# FULL_CB_Servo_REV_C.net
KiCad netlist of a schematic drawn in Altium Designer
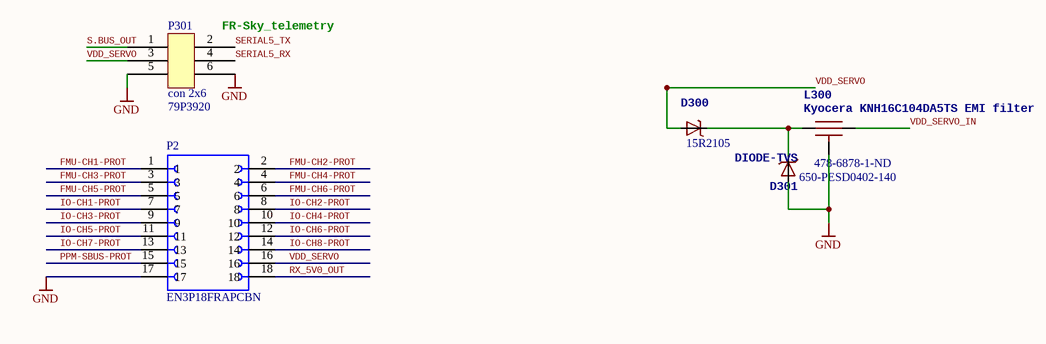
[diagram p0: FULL_CB_Servo_REV_C.SchDoc]

(export (version "E")
  (design (tool "Eeschema 10.0.6"))
  (components
    (comp (ref "D300")
      (value "MSS1P4-M3")
      (footprint "MICROSMP")
      (description "Diode, Schottky, 40V, 1A, MicroSMP, SMD")
      (fields (field (name "SUPPLIER PART NUMBER 1") "15R2105"))
      (libsource (lib "CB_REV_C") (part "DIODE-SCHOTTKY_MSMP"))
    )
    (comp (ref "D301")
      (value "DIODE-TVS")
      (footprint "0402-TVS")
      (description "Diode, TVS, 14VWM, 40VC, 0402, SMD")
      (fields (field (name "SUPPLIER PART NUMBER 1") "650-PESD0402-140"))
      (libsource (lib "CB_REV_C") (part "DIODE-TVS"))
    )
    (comp (ref "L300")
      (value "Kyocera KNH16C104DA5TS EMI filter")
      (footprint "KYOCERA-KNH16-DA")
      (description "Capacitor, Filter, 0.1uF, 25V, 2A, 0603, SMD")
      (fields (field (name "SUPPLIER PART NUMBER 1") "478-6878-1-ND"))
      (libsource (lib "CB_REV_C") (part "KNH16C104DA5TS"))
    )
    (comp (ref "P2")
      (value "EN3P18FRAPCBN")
      (footprint "SWITCHCRAFT_EN3P18FRAPCBN")
      (libsource (lib "CB_REV_C") (part "EN3P18FRAPCBN"))
    )
    (comp (ref "P301")
      (value "con 2x6")
      (footprint "TSW-103-07-G-D")
      (description "Connector, Header, 6Pos, 2.54MM, Vert, THT, Au")
      (fields (field (name "SUPPLIER PART NUMBER 1") "79P3920"))
      (libsource (lib "CB_REV_C") (part "con 2x6"))
    )
  )
  (nets
    (net (code "1") (name "/FMU-CH1-PROT") (class "Default")
      (node (ref "P2") (pin "1") (pinfunction "1_1") (pintype "passive"))
    )
    (net (code "2") (name "/FMU-CH2-PROT") (class "Default")
      (node (ref "P2") (pin "2") (pinfunction "2_2") (pintype "passive"))
    )
    (net (code "3") (name "/FMU-CH3-PROT") (class "Default")
      (node (ref "P2") (pin "3") (pinfunction "3_3") (pintype "passive"))
    )
    (net (code "4") (name "/FMU-CH4-PROT") (class "Default")
      (node (ref "P2") (pin "4") (pinfunction "4_4") (pintype "passive"))
    )
    (net (code "5") (name "/FMU-CH5-PROT") (class "Default")
      (node (ref "P2") (pin "5") (pinfunction "5_5") (pintype "passive"))
    )
    (net (code "6") (name "/FMU-CH6-PROT") (class "Default")
      (node (ref "P2") (pin "6") (pinfunction "6_6") (pintype "passive"))
    )
    (net (code "7") (name "/IO-CH1-PROT") (class "Default")
      (node (ref "P2") (pin "7") (pinfunction "7_7") (pintype "passive"))
    )
    (net (code "8") (name "/IO-CH2-PROT") (class "Default")
      (node (ref "P2") (pin "8") (pinfunction "8_8") (pintype "passive"))
    )
    (net (code "9") (name "/IO-CH3-PROT") (class "Default")
      (node (ref "P2") (pin "9") (pinfunction "9_9") (pintype "passive"))
    )
    (net (code "10") (name "/IO-CH4-PROT") (class "Default")
      (node (ref "P2") (pin "10") (pinfunction "10_10") (pintype "passive"))
    )
    (net (code "11") (name "/IO-CH5-PROT") (class "Default")
      (node (ref "P2") (pin "11") (pinfunction "11_11") (pintype "passive"))
    )
    (net (code "12") (name "/IO-CH6-PROT") (class "Default")
      (node (ref "P2") (pin "12") (pinfunction "12_12") (pintype "passive"))
    )
    (net (code "13") (name "/IO-CH7-PROT") (class "Default")
      (node (ref "P2") (pin "13") (pinfunction "13_13") (pintype "passive"))
    )
    (net (code "14") (name "/IO-CH8-PROT") (class "Default")
      (node (ref "P2") (pin "14") (pinfunction "14_14") (pintype "passive"))
    )
    (net (code "15") (name "/PPM-SBUS-PROT") (class "Default")
      (node (ref "P2") (pin "15") (pinfunction "15_15") (pintype "passive"))
    )
    (net (code "16") (name "/RX_5V0_OUT") (class "Default")
      (node (ref "P2") (pin "18") (pinfunction "18_18") (pintype "passive"))
    )
    (net (code "17") (name "/S.BUS_OUT") (class "Default")
      (node (ref "P301") (pin "1") (pinfunction "1_1") (pintype "passive"))
    )
    (net (code "18") (name "/SERIAL5_RX") (class "Default")
      (node (ref "P301") (pin "4") (pinfunction "4_4") (pintype "passive"))
    )
    (net (code "19") (name "/SERIAL5_TX") (class "Default")
      (node (ref "P301") (pin "2") (pinfunction "2_2") (pintype "passive"))
    )
    (net (code "20") (name "/VDD_SERVO") (class "Default")
      (node (ref "D300") (pin "ANODE") (pinfunction "A_ANODE") (pintype "passive"))
      (node (ref "P2") (pin "16") (pinfunction "16_16") (pintype "passive"))
      (node (ref "P301") (pin "3") (pinfunction "3_3") (pintype "passive"))
    )
    (net (code "21") (name "/VDD_SERVO_IN") (class "Default")
      (node (ref "L300") (pin "P$2") (pinfunction "P$2_P$2") (pintype "passive"))
    )
    (net (code "22") (name "GND") (class "Default")
      (node (ref "D301") (pin "A") (pinfunction "A_A") (pintype "passive"))
      (node (ref "L300") (pin "GND") (pinfunction "GND_GND") (pintype "passive"))
      (node (ref "P2") (pin "17") (pinfunction "17_17") (pintype "passive"))
      (node (ref "P301") (pin "5") (pinfunction "5_5") (pintype "passive"))
      (node (ref "P301") (pin "6") (pinfunction "6_6") (pintype "passive"))
    )
    (net (code "23") (name "Net-(D300-C)") (class "Default")
      (node (ref "D300") (pin "CATHODE") (pinfunction "C_CATHODE") (pintype "passive"))
      (node (ref "D301") (pin "C") (pinfunction "C_C") (pintype "passive"))
      (node (ref "L300") (pin "P$1") (pinfunction "P$1_P$1") (pintype "passive"))
    )
  )
)
